# pcb-pick-plaz-feeder.net
KiCad netlist of a schematic drawn in EAGLE
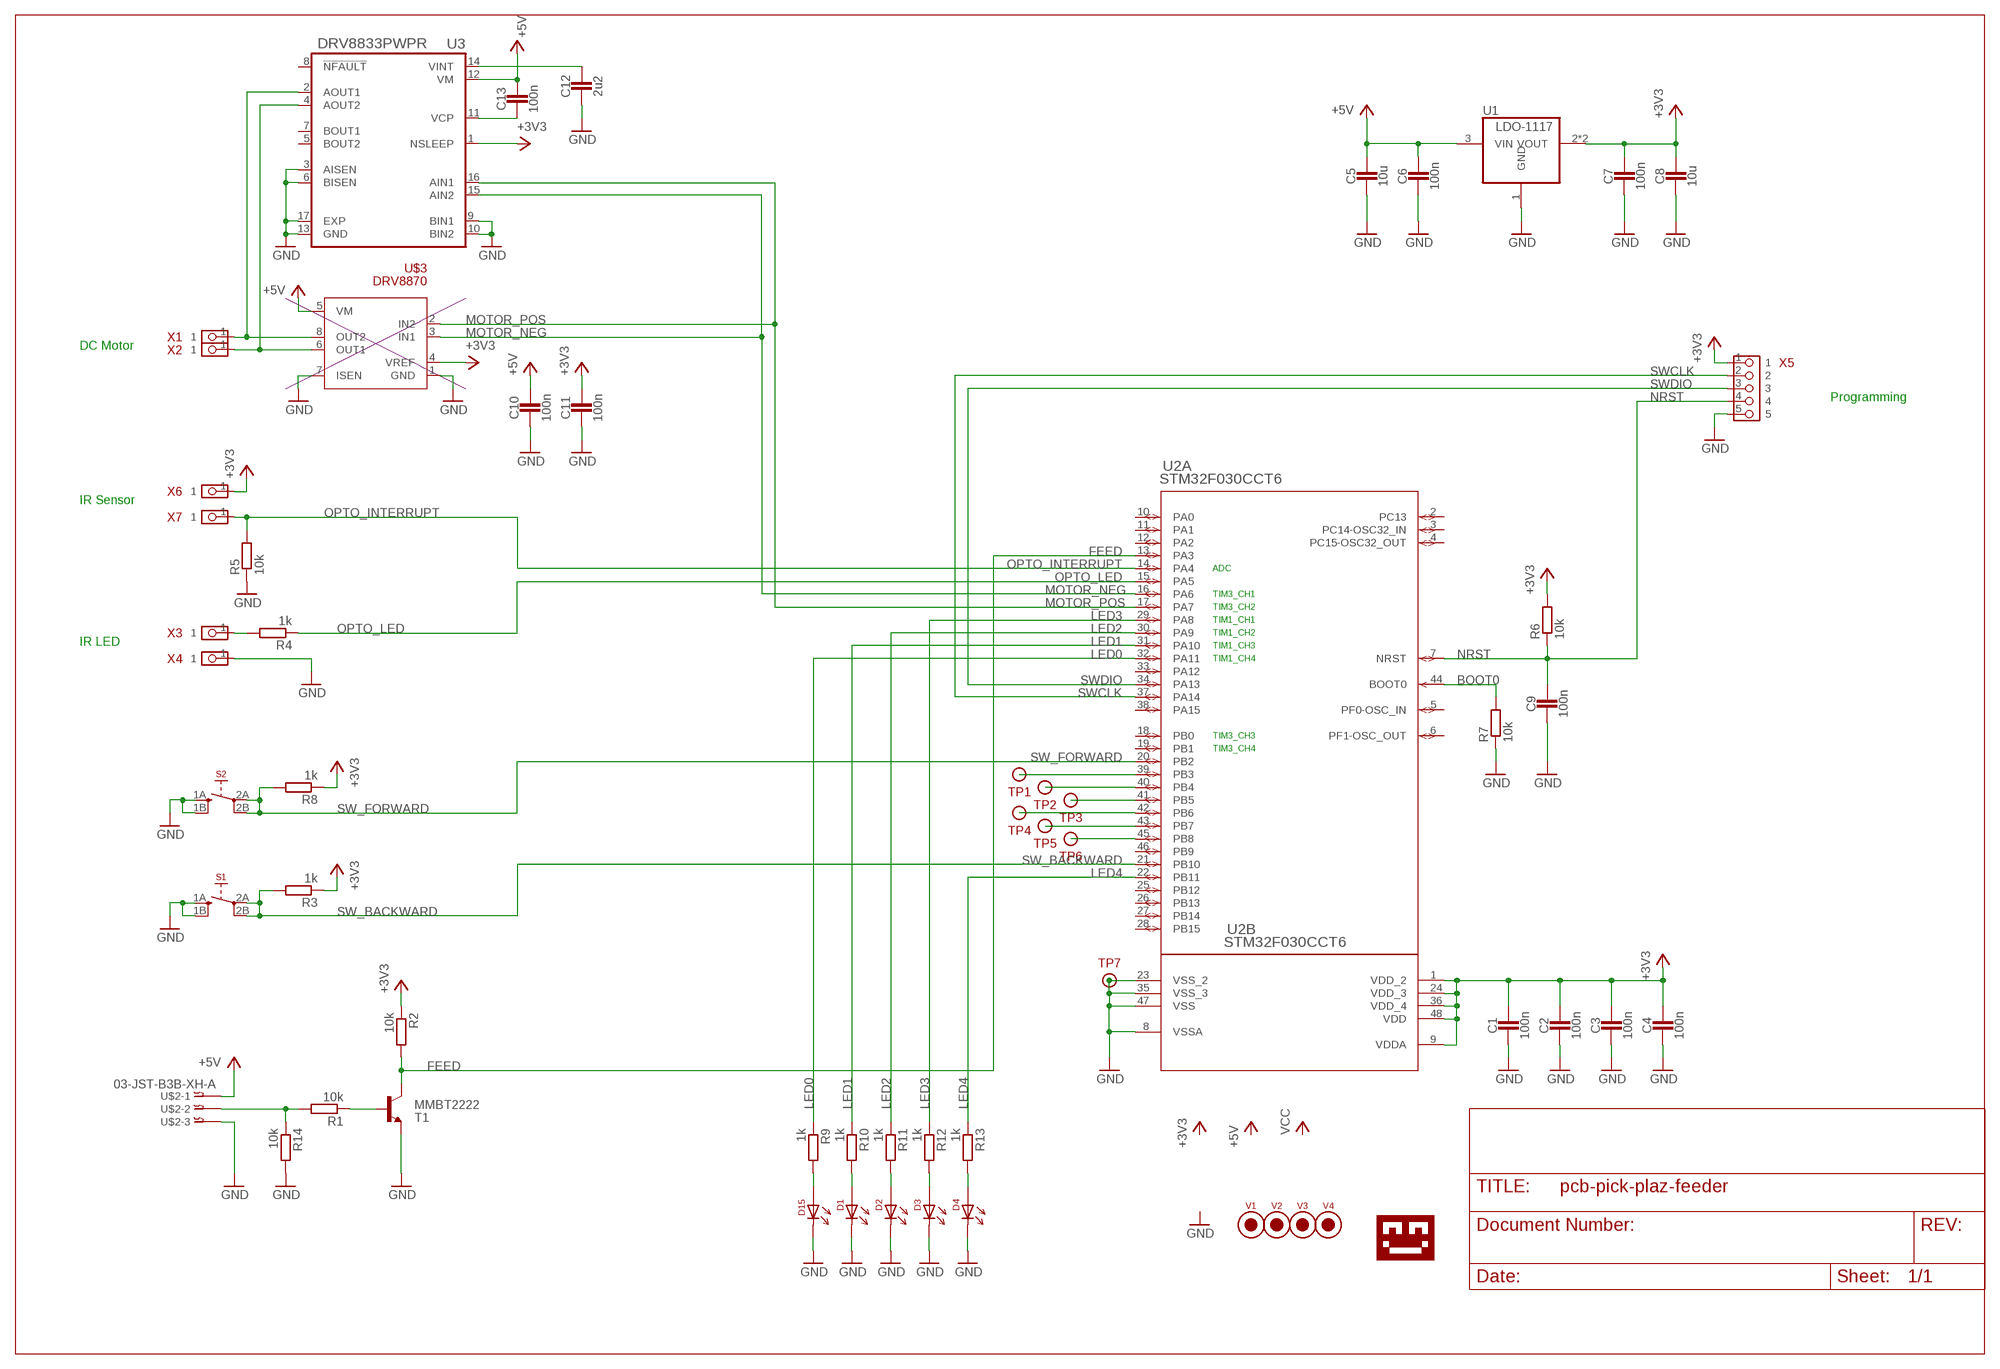
[diagram p0: schematic, sheet 1]

(export (version "E")
  (design (tool "Eeschema 10.0.6"))
  (components
    (comp (ref "C1")
      (value "100n")
      (footprint "eagle-import:0603_CAP")
      (libsource (lib "eagle-import") (part "CAPACITOR0603_CAP"))
    )
    (comp (ref "C2")
      (value "100n")
      (footprint "eagle-import:0603_CAP")
      (libsource (lib "eagle-import") (part "CAPACITOR0603_CAP"))
    )
    (comp (ref "C3")
      (value "100n")
      (footprint "eagle-import:0603_CAP")
      (libsource (lib "eagle-import") (part "CAPACITOR0603_CAP"))
    )
    (comp (ref "C4")
      (value "100n")
      (footprint "eagle-import:0603_CAP")
      (libsource (lib "eagle-import") (part "CAPACITOR0603_CAP"))
    )
    (comp (ref "C5")
      (value "10u")
      (footprint "eagle-import:0805_CAP")
      (libsource (lib "eagle-import") (part "CAPACITOR0805_CAP"))
    )
    (comp (ref "C6")
      (value "100n")
      (footprint "eagle-import:0603_CAP")
      (libsource (lib "eagle-import") (part "CAPACITOR0603_CAP"))
    )
    (comp (ref "C7")
      (value "100n")
      (footprint "eagle-import:0603_CAP")
      (libsource (lib "eagle-import") (part "CAPACITOR0603_CAP"))
    )
    (comp (ref "C8")
      (value "10u")
      (footprint "eagle-import:0805_CAP")
      (libsource (lib "eagle-import") (part "CAPACITOR0805_CAP"))
    )
    (comp (ref "C9")
      (value "100n")
      (footprint "eagle-import:0603_CAP")
      (libsource (lib "eagle-import") (part "CAPACITOR0603_CAP"))
    )
    (comp (ref "C10")
      (value "100n")
      (footprint "eagle-import:0603_CAP")
      (libsource (lib "eagle-import") (part "CAPACITOR0603_CAP"))
    )
    (comp (ref "C11")
      (value "100n")
      (footprint "eagle-import:0603_CAP")
      (libsource (lib "eagle-import") (part "CAPACITOR0603_CAP"))
    )
    (comp (ref "C12")
      (value "2u2")
      (footprint "eagle-import:0805_CAP")
      (libsource (lib "eagle-import") (part "CAPACITOR0805_CAP"))
    )
    (comp (ref "C13")
      (value "100n")
      (footprint "eagle-import:0603_CAP")
      (libsource (lib "eagle-import") (part "CAPACITOR0603_CAP"))
    )
    (comp (ref "D1")
      (value "LED-0805")
      (footprint "eagle-import:0805-DOT")
      (libsource (lib "eagle-import") (part "LED-0805"))
    )
    (comp (ref "D2")
      (value "LED-0805")
      (footprint "eagle-import:0805-DOT")
      (libsource (lib "eagle-import") (part "LED-0805"))
    )
    (comp (ref "D3")
      (value "LED-0805")
      (footprint "eagle-import:0805-DOT")
      (libsource (lib "eagle-import") (part "LED-0805"))
    )
    (comp (ref "D4")
      (value "LED-0805")
      (footprint "eagle-import:0805-DOT")
      (libsource (lib "eagle-import") (part "LED-0805"))
    )
    (comp (ref "D15")
      (value "LED-0805")
      (footprint "eagle-import:0805-DOT")
      (libsource (lib "eagle-import") (part "LED-0805"))
    )
    (comp (ref "R1")
      (value "10k")
      (footprint "eagle-import:0603-RES")
      (libsource (lib "eagle-import") (part "RESISTOR0603_RES"))
    )
    (comp (ref "R2")
      (value "10k")
      (footprint "eagle-import:0603-RES")
      (libsource (lib "eagle-import") (part "RESISTOR0603_RES"))
    )
    (comp (ref "R3")
      (value "1k")
      (footprint "eagle-import:0603-RES")
      (libsource (lib "eagle-import") (part "RESISTOR0603_RES"))
    )
    (comp (ref "R4")
      (value "1k")
      (footprint "eagle-import:0603-RES")
      (libsource (lib "eagle-import") (part "RESISTOR0603_RES"))
    )
    (comp (ref "R5")
      (value "10k")
      (footprint "eagle-import:0603-RES")
      (libsource (lib "eagle-import") (part "RESISTOR0603_RES"))
    )
    (comp (ref "R6")
      (value "10k")
      (footprint "eagle-import:0603-RES")
      (libsource (lib "eagle-import") (part "RESISTOR0603_RES"))
    )
    (comp (ref "R7")
      (value "10k")
      (footprint "eagle-import:0603-RES")
      (libsource (lib "eagle-import") (part "RESISTOR0603_RES"))
    )
    (comp (ref "R8")
      (value "1k")
      (footprint "eagle-import:0603-RES")
      (libsource (lib "eagle-import") (part "RESISTOR0603_RES"))
    )
    (comp (ref "R9")
      (value "1k")
      (footprint "eagle-import:0603-RES")
      (libsource (lib "eagle-import") (part "RESISTOR0603_RES"))
    )
    (comp (ref "R10")
      (value "1k")
      (footprint "eagle-import:0603-RES")
      (libsource (lib "eagle-import") (part "RESISTOR0603_RES"))
    )
    (comp (ref "R11")
      (value "1k")
      (footprint "eagle-import:0603-RES")
      (libsource (lib "eagle-import") (part "RESISTOR0603_RES"))
    )
    (comp (ref "R12")
      (value "1k")
      (footprint "eagle-import:0603-RES")
      (libsource (lib "eagle-import") (part "RESISTOR0603_RES"))
    )
    (comp (ref "R13")
      (value "1k")
      (footprint "eagle-import:0603-RES")
      (libsource (lib "eagle-import") (part "RESISTOR0603_RES"))
    )
    (comp (ref "R14")
      (value "10k")
      (footprint "eagle-import:0603-RES")
      (libsource (lib "eagle-import") (part "RESISTOR0603_RES"))
    )
    (comp (ref "S1")
      (value "SWITCH_2PD")
      (footprint "eagle-import:SWITCH_WH")
      (libsource (lib "eagle-import") (part "SWITCH_2PD"))
    )
    (comp (ref "S2")
      (value "SWITCH_2PD")
      (footprint "eagle-import:SWITCH_WH")
      (libsource (lib "eagle-import") (part "SWITCH_2PD"))
    )
    (comp (ref "T1")
      (value "MMBT2222")
      (footprint "eagle-import:SOT23-BEC")
      (libsource (lib "eagle-import") (part "-NPN-SOT23-BECMMBT2222ALT1"))
    )
    (comp (ref "TP1")
      (value "TESTPIN")
      (footprint "eagle-import:PIN-SMD-1X1-TEST_1M5")
      (libsource (lib "eagle-import") (part "TESTPIN"))
    )
    (comp (ref "TP2")
      (value "TESTPIN")
      (footprint "eagle-import:PIN-SMD-1X1-TEST_1M5")
      (libsource (lib "eagle-import") (part "TESTPIN"))
    )
    (comp (ref "TP3")
      (value "TESTPIN")
      (footprint "eagle-import:PIN-SMD-1X1-TEST_1M5")
      (libsource (lib "eagle-import") (part "TESTPIN"))
    )
    (comp (ref "TP4")
      (value "TESTPIN")
      (footprint "eagle-import:PIN-SMD-1X1-TEST_1M5")
      (libsource (lib "eagle-import") (part "TESTPIN"))
    )
    (comp (ref "TP5")
      (value "TESTPIN")
      (footprint "eagle-import:PIN-SMD-1X1-TEST_1M5")
      (libsource (lib "eagle-import") (part "TESTPIN"))
    )
    (comp (ref "TP6")
      (value "TESTPIN")
      (footprint "eagle-import:PIN-SMD-1X1-TEST_1M5")
      (libsource (lib "eagle-import") (part "TESTPIN"))
    )
    (comp (ref "TP7")
      (value "TESTPIN")
      (footprint "eagle-import:PIN-SMD-1X1-TEST_1M5")
      (libsource (lib "eagle-import") (part "TESTPIN"))
    )
    (comp (ref "U$1")
      (value "LOGO-TOBENG-1MM-FINISH")
      (footprint "eagle-import:TOBENG-1MM-FINISH")
      (libsource (lib "eagle-import") (part "LOGO-TOBENG-1MM-FINISH"))
    )
    (comp (ref "U$2")
      (value "03-JST-B3B-XH-A")
      (footprint "eagle-import:B3B-XH")
      (libsource (lib "eagle-import") (part "03-JST-B3B-XH-A"))
    )
    (comp (ref "U$3")
      (value "DRV8870")
      (footprint "eagle-import:SOIC-8")
      (libsource (lib "eagle-import") (part "DRV8870"))
    )
    (comp (ref "U1")
      (value "LDO-1117")
      (footprint "eagle-import:SOT-89")
      (libsource (lib "eagle-import") (part "LDO-1117"))
    )
    (comp (ref "U2")
      (value "STM32F030CCT6")
      (footprint "eagle-import:LQFP48-7X7MM")
      (fields (field (name "COPYRIGHT") "Copyright (C) 2018 Accelerated Designs. All rights reserved"))
      (libsource (lib "eagle-import") (part "STM32F030CCT6"))
    )
    (comp (ref "U3")
      (value "DRV8833PWPR")
      (footprint "eagle-import:IC_DRV8833PWPR")
      (fields (field (name "MF") "Texas Instruments"))
      (libsource (lib "eagle-import") (part "DRV8833PWPR"))
    )
    (comp (ref "V1")
      (value "FIDUCIAL2MM")
      (footprint "eagle-import:FIDUCIAL_2MM")
      (libsource (lib "eagle-import") (part "FIDUCIAL2MM"))
    )
    (comp (ref "V2")
      (value "FIDUCIAL2MM")
      (footprint "eagle-import:FIDUCIAL_2MM")
      (libsource (lib "eagle-import") (part "FIDUCIAL2MM"))
    )
    (comp (ref "V3")
      (value "FIDUCIAL2MM")
      (footprint "eagle-import:FIDUCIAL_2MM")
      (libsource (lib "eagle-import") (part "FIDUCIAL2MM"))
    )
    (comp (ref "V4")
      (value "FIDUCIAL2MM")
      (footprint "eagle-import:FIDUCIAL_2MM")
      (libsource (lib "eagle-import") (part "FIDUCIAL2MM"))
    )
    (comp (ref "X1")
      (value "PIN_1X1SMD_BIG_L")
      (footprint "eagle-import:PIN_1X1_SMD_BIG_L")
      (libsource (lib "eagle-import") (part "PIN_1X1SMD_BIG_L"))
    )
    (comp (ref "X2")
      (value "PIN_1X1SMD_BIG_L")
      (footprint "eagle-import:PIN_1X1_SMD_BIG_L")
      (libsource (lib "eagle-import") (part "PIN_1X1SMD_BIG_L"))
    )
    (comp (ref "X3")
      (value "PIN_1X1SMD_BIG_L")
      (footprint "eagle-import:PIN_1X1_SMD_BIG_L")
      (libsource (lib "eagle-import") (part "PIN_1X1SMD_BIG_L"))
    )
    (comp (ref "X4")
      (value "PIN_1X1SMD_BIG_L")
      (footprint "eagle-import:PIN_1X1_SMD_BIG_L")
      (libsource (lib "eagle-import") (part "PIN_1X1SMD_BIG_L"))
    )
    (comp (ref "X5")
      (value "PIN_5X1HD")
      (footprint "eagle-import:PIN_5X1_HD")
      (libsource (lib "eagle-import") (part "PIN_5X1HD"))
    )
    (comp (ref "X6")
      (value "PIN_1X1SMD_BIG_L")
      (footprint "eagle-import:PIN_1X1_SMD_BIG_L")
      (libsource (lib "eagle-import") (part "PIN_1X1SMD_BIG_L"))
    )
    (comp (ref "X7")
      (value "PIN_1X1SMD_BIG_L")
      (footprint "eagle-import:PIN_1X1_SMD_BIG_L")
      (libsource (lib "eagle-import") (part "PIN_1X1SMD_BIG_L"))
    )
  )
  (nets
    (net (code "1") (name "+3V3") (class "Default")
      (node (ref "C1") (pin "1") (pinfunction "1_1") (pintype "bidirectional"))
      (node (ref "C11") (pin "1") (pinfunction "1_1") (pintype "bidirectional"))
      (node (ref "C2") (pin "1") (pinfunction "1_1") (pintype "bidirectional"))
      (node (ref "C3") (pin "1") (pinfunction "1_1") (pintype "bidirectional"))
      (node (ref "C4") (pin "1") (pinfunction "1_1") (pintype "bidirectional"))
      (node (ref "C7") (pin "1") (pinfunction "1_1") (pintype "bidirectional"))
      (node (ref "C8") (pin "P$1") (pinfunction "1_P$1") (pintype "bidirectional"))
      (node (ref "R2") (pin "1") (pinfunction "1_1") (pintype "passive"))
      (node (ref "R3") (pin "1") (pinfunction "1_1") (pintype "passive"))
      (node (ref "R6") (pin "2") (pinfunction "2_2") (pintype "passive"))
      (node (ref "R8") (pin "1") (pinfunction "1_1") (pintype "passive"))
      (node (ref "U$3") (pin "4") (pinfunction "VREF_4") (pintype "bidirectional"))
      (node (ref "U1") (pin "2") (pinfunction "VOUT_2") (pintype "output"))
      (node (ref "U1") (pin "2@1") (pinfunction "VOUT_2@1") (pintype "output"))
      (node (ref "U2") (pin "1") (pinfunction "VDD_2_1") (pintype "power_in"))
      (node (ref "U2") (pin "24") (pinfunction "VDD_3_24") (pintype "power_in"))
      (node (ref "U2") (pin "36") (pinfunction "VDD_4_36") (pintype "power_in"))
      (node (ref "U2") (pin "48") (pinfunction "VDD_48") (pintype "power_in"))
      (node (ref "U2") (pin "9") (pinfunction "VDDA_9") (pintype "power_in"))
      (node (ref "U3") (pin "1") (pinfunction "NSLEEP_1") (pintype "input"))
      (node (ref "X5") (pin "1") (pinfunction "1_1") (pintype "bidirectional"))
      (node (ref "X6") (pin "1") (pinfunction "1_1") (pintype "bidirectional"))
    )
    (net (code "2") (name "+5V") (class "Default")
      (node (ref "C10") (pin "1") (pinfunction "1_1") (pintype "bidirectional"))
      (node (ref "C13") (pin "1") (pinfunction "1_1") (pintype "bidirectional"))
      (node (ref "C5") (pin "P$1") (pinfunction "1_P$1") (pintype "bidirectional"))
      (node (ref "C6") (pin "1") (pinfunction "1_1") (pintype "bidirectional"))
      (node (ref "U$2") (pin "P$1") (pinfunction "1_P$1") (pintype "passive"))
      (node (ref "U$3") (pin "5") (pinfunction "VM_5") (pintype "bidirectional"))
      (node (ref "U1") (pin "3") (pinfunction "VIN_3") (pintype "input"))
      (node (ref "U3") (pin "12") (pinfunction "VM_12") (pintype "power_in"))
    )
    (net (code "3") (name "/BOOT0") (class "Default")
      (node (ref "R7") (pin "2") (pinfunction "2_2") (pintype "passive"))
      (node (ref "U2") (pin "44") (pinfunction "BOOT0_44") (pintype "input"))
    )
    (net (code "4") (name "/FEED") (class "Default")
      (node (ref "R2") (pin "2") (pinfunction "2_2") (pintype "passive"))
      (node (ref "T1") (pin "C") (pinfunction "C_C") (pintype "passive"))
      (node (ref "U2") (pin "13") (pinfunction "PA3_13") (pintype "bidirectional"))
    )
    (net (code "5") (name "/LED0") (class "Default")
      (node (ref "R9") (pin "1") (pinfunction "1_1") (pintype "passive"))
      (node (ref "U2") (pin "32") (pinfunction "PA11_32") (pintype "bidirectional"))
    )
    (net (code "6") (name "/LED1") (class "Default")
      (node (ref "R10") (pin "1") (pinfunction "1_1") (pintype "passive"))
      (node (ref "U2") (pin "31") (pinfunction "PA10_31") (pintype "bidirectional"))
    )
    (net (code "7") (name "/LED2") (class "Default")
      (node (ref "R11") (pin "1") (pinfunction "1_1") (pintype "passive"))
      (node (ref "U2") (pin "30") (pinfunction "PA9_30") (pintype "bidirectional"))
    )
    (net (code "8") (name "/LED3") (class "Default")
      (node (ref "R12") (pin "1") (pinfunction "1_1") (pintype "passive"))
      (node (ref "U2") (pin "29") (pinfunction "PA8_29") (pintype "bidirectional"))
    )
    (net (code "9") (name "/LED4") (class "Default")
      (node (ref "R13") (pin "1") (pinfunction "1_1") (pintype "passive"))
      (node (ref "U2") (pin "22") (pinfunction "PB11_22") (pintype "bidirectional"))
    )
    (net (code "10") (name "/MOTOR_NEG") (class "Default")
      (node (ref "U$3") (pin "3") (pinfunction "IN1_3") (pintype "bidirectional"))
      (node (ref "U2") (pin "16") (pinfunction "PA6_16") (pintype "bidirectional"))
      (node (ref "U3") (pin "15") (pinfunction "AIN2_15") (pintype "input"))
    )
    (net (code "11") (name "/MOTOR_POS") (class "Default")
      (node (ref "U$3") (pin "2") (pinfunction "IN2_2") (pintype "bidirectional"))
      (node (ref "U2") (pin "17") (pinfunction "PA7_17") (pintype "bidirectional"))
      (node (ref "U3") (pin "16") (pinfunction "AIN1_16") (pintype "input"))
    )
    (net (code "12") (name "/NRST") (class "Default")
      (node (ref "C9") (pin "1") (pinfunction "1_1") (pintype "bidirectional"))
      (node (ref "R6") (pin "1") (pinfunction "1_1") (pintype "passive"))
      (node (ref "U2") (pin "7") (pinfunction "NRST_7") (pintype "bidirectional"))
      (node (ref "X5") (pin "4") (pinfunction "4_4") (pintype "bidirectional"))
    )
    (net (code "13") (name "/OPTO_INTERRUPT") (class "Default")
      (node (ref "R5") (pin "2") (pinfunction "2_2") (pintype "passive"))
      (node (ref "U2") (pin "14") (pinfunction "PA4_14") (pintype "bidirectional"))
      (node (ref "X7") (pin "1") (pinfunction "1_1") (pintype "bidirectional"))
    )
    (net (code "14") (name "/OPTO_LED") (class "Default")
      (node (ref "R4") (pin "1") (pinfunction "1_1") (pintype "passive"))
      (node (ref "U2") (pin "15") (pinfunction "PA5_15") (pintype "bidirectional"))
    )
    (net (code "15") (name "/SWCLK") (class "Default")
      (node (ref "U2") (pin "37") (pinfunction "PA14_37") (pintype "bidirectional"))
      (node (ref "X5") (pin "2") (pinfunction "2_2") (pintype "bidirectional"))
    )
    (net (code "16") (name "/SWDIO") (class "Default")
      (node (ref "U2") (pin "34") (pinfunction "PA13_34") (pintype "bidirectional"))
      (node (ref "X5") (pin "3") (pinfunction "3_3") (pintype "bidirectional"))
    )
    (net (code "17") (name "/SW_BACKWARD") (class "Default")
      (node (ref "R3") (pin "2") (pinfunction "2_2") (pintype "passive"))
      (node (ref "S1") (pin "2A") (pinfunction "3_2A") (pintype "bidirectional"))
      (node (ref "S1") (pin "2B") (pinfunction "4_2B") (pintype "bidirectional"))
      (node (ref "U2") (pin "21") (pinfunction "PB10_21") (pintype "bidirectional"))
    )
    (net (code "18") (name "/SW_FORWARD") (class "Default")
      (node (ref "R8") (pin "2") (pinfunction "2_2") (pintype "passive"))
      (node (ref "S2") (pin "2A") (pinfunction "3_2A") (pintype "bidirectional"))
      (node (ref "S2") (pin "2B") (pinfunction "4_2B") (pintype "bidirectional"))
      (node (ref "U2") (pin "20") (pinfunction "PB2_20") (pintype "bidirectional"))
    )
    (net (code "19") (name "GND") (class "Default")
      (node (ref "C1") (pin "2") (pinfunction "2_2") (pintype "bidirectional"))
      (node (ref "C10") (pin "2") (pinfunction "2_2") (pintype "bidirectional"))
      (node (ref "C11") (pin "2") (pinfunction "2_2") (pintype "bidirectional"))
      (node (ref "C12") (pin "P$2") (pinfunction "2_P$2") (pintype "bidirectional"))
      (node (ref "C2") (pin "2") (pinfunction "2_2") (pintype "bidirectional"))
      (node (ref "C3") (pin "2") (pinfunction "2_2") (pintype "bidirectional"))
      (node (ref "C4") (pin "2") (pinfunction "2_2") (pintype "bidirectional"))
      (node (ref "C5") (pin "P$2") (pinfunction "2_P$2") (pintype "bidirectional"))
      (node (ref "C6") (pin "2") (pinfunction "2_2") (pintype "bidirectional"))
      (node (ref "C7") (pin "2") (pinfunction "2_2") (pintype "bidirectional"))
      (node (ref "C8") (pin "P$2") (pinfunction "2_P$2") (pintype "bidirectional"))
      (node (ref "C9") (pin "2") (pinfunction "2_2") (pintype "bidirectional"))
      (node (ref "D1") (pin "2") (pinfunction "2_2") (pintype "bidirectional"))
      (node (ref "D15") (pin "2") (pinfunction "2_2") (pintype "bidirectional"))
      (node (ref "D2") (pin "2") (pinfunction "2_2") (pintype "bidirectional"))
      (node (ref "D3") (pin "2") (pinfunction "2_2") (pintype "bidirectional"))
      (node (ref "D4") (pin "2") (pinfunction "2_2") (pintype "bidirectional"))
      (node (ref "R14") (pin "2") (pinfunction "2_2") (pintype "passive"))
      (node (ref "R5") (pin "1") (pinfunction "1_1") (pintype "passive"))
      (node (ref "R7") (pin "1") (pinfunction "1_1") (pintype "passive"))
      (node (ref "S1") (pin "1A") (pinfunction "1_1A") (pintype "bidirectional"))
      (node (ref "S1") (pin "1B") (pinfunction "2_1B") (pintype "bidirectional"))
      (node (ref "S2") (pin "1A") (pinfunction "1_1A") (pintype "bidirectional"))
      (node (ref "S2") (pin "1B") (pinfunction "2_1B") (pintype "bidirectional"))
      (node (ref "T1") (pin "E") (pinfunction "E_E") (pintype "passive"))
      (node (ref "TP7") (pin "1") (pinfunction "1_1") (pintype "bidirectional"))
      (node (ref "U$2") (pin "P$3") (pinfunction "1_P$3") (pintype "passive"))
      (node (ref "U$3") (pin "1") (pinfunction "GND_1") (pintype "bidirectional"))
      (node (ref "U$3") (pin "7") (pinfunction "ISEN_7") (pintype "bidirectional"))
      (node (ref "U1") (pin "1") (pinfunction "GND_1") (pintype "power_in"))
      (node (ref "U2") (pin "23") (pinfunction "VSS_2_23") (pintype "power_in"))
      (node (ref "U2") (pin "35") (pinfunction "VSS_3_35") (pintype "power_in"))
      (node (ref "U2") (pin "47") (pinfunction "VSS_47") (pintype "power_in"))
      (node (ref "U2") (pin "8") (pinfunction "VSSA_8") (pintype "power_in"))
      (node (ref "U3") (pin "10") (pinfunction "BIN2_10") (pintype "input"))
      (node (ref "U3") (pin "13") (pinfunction "GND_13") (pintype "power_in"))
      (node (ref "U3") (pin "17") (pinfunction "EXP_17") (pintype "passive"))
      (node (ref "U3") (pin "3") (pinfunction "AISEN_3") (pintype "bidirectional"))
      (node (ref "U3") (pin "6") (pinfunction "BISEN_6") (pintype "bidirectional"))
      (node (ref "U3") (pin "9") (pinfunction "BIN1_9") (pintype "input"))
      (node (ref "X4") (pin "1") (pinfunction "1_1") (pintype "bidirectional"))
      (node (ref "X5") (pin "5") (pinfunction "5_5") (pintype "bidirectional"))
    )
    (net (code "20") (name "Net-(C12-1)") (class "Default")
      (node (ref "C12") (pin "P$1") (pinfunction "1_P$1") (pintype "bidirectional"))
      (node (ref "U3") (pin "14") (pinfunction "VINT_14") (pintype "power_in"))
    )
    (net (code "21") (name "Net-(D1-Pad1)") (class "Default")
      (node (ref "D1") (pin "1") (pinfunction "1_1") (pintype "bidirectional"))
      (node (ref "R10") (pin "2") (pinfunction "2_2") (pintype "passive"))
    )
    (net (code "22") (name "Net-(D2-Pad1)") (class "Default")
      (node (ref "D2") (pin "1") (pinfunction "1_1") (pintype "bidirectional"))
      (node (ref "R11") (pin "2") (pinfunction "2_2") (pintype "passive"))
    )
    (net (code "23") (name "Net-(D3-Pad1)") (class "Default")
      (node (ref "D3") (pin "1") (pinfunction "1_1") (pintype "bidirectional"))
      (node (ref "R12") (pin "2") (pinfunction "2_2") (pintype "passive"))
    )
    (net (code "24") (name "Net-(D4-Pad1)") (class "Default")
      (node (ref "D4") (pin "1") (pinfunction "1_1") (pintype "bidirectional"))
      (node (ref "R13") (pin "2") (pinfunction "2_2") (pintype "passive"))
    )
    (net (code "25") (name "Net-(D15-Pad1)") (class "Default")
      (node (ref "D15") (pin "1") (pinfunction "1_1") (pintype "bidirectional"))
      (node (ref "R9") (pin "2") (pinfunction "2_2") (pintype "passive"))
    )
    (net (code "26") (name "Net-(R1-Pad1)") (class "Default")
      (node (ref "R1") (pin "1") (pinfunction "1_1") (pintype "passive"))
      (node (ref "T1") (pin "B") (pinfunction "B_B") (pintype "passive"))
    )
    (net (code "27") (name "Net-(R4-Pad2)") (class "Default")
      (node (ref "R4") (pin "2") (pinfunction "2_2") (pintype "passive"))
      (node (ref "X3") (pin "1") (pinfunction "1_1") (pintype "bidirectional"))
    )
    (net (code "28") (name "Net-(U$2B-1)") (class "Default")
      (node (ref "R1") (pin "2") (pinfunction "2_2") (pintype "passive"))
      (node (ref "R14") (pin "1") (pinfunction "1_1") (pintype "passive"))
      (node (ref "U$2") (pin "P$2") (pinfunction "1_P$2") (pintype "passive"))
    )
    (net (code "29") (name "Net-(U$3-OUT1)") (class "Default")
      (node (ref "U$3") (pin "6") (pinfunction "OUT1_6") (pintype "bidirectional"))
      (node (ref "U3") (pin "4") (pinfunction "AOUT2_4") (pintype "output"))
      (node (ref "X2") (pin "1") (pinfunction "1_1") (pintype "bidirectional"))
    )
    (net (code "30") (name "Net-(U$3-OUT2)") (class "Default")
      (node (ref "U$3") (pin "8") (pinfunction "OUT2_8") (pintype "bidirectional"))
      (node (ref "U3") (pin "2") (pinfunction "AOUT1_2") (pintype "output"))
      (node (ref "X1") (pin "1") (pinfunction "1_1") (pintype "bidirectional"))
    )
    (net (code "31") (name "Net-(U2A-PB3)") (class "Default")
      (node (ref "TP1") (pin "1") (pinfunction "1_1") (pintype "bidirectional"))
      (node (ref "U2") (pin "39") (pinfunction "PB3_39") (pintype "bidirectional"))
    )
    (net (code "32") (name "Net-(U2A-PB4)") (class "Default")
      (node (ref "TP2") (pin "1") (pinfunction "1_1") (pintype "bidirectional"))
      (node (ref "U2") (pin "40") (pinfunction "PB4_40") (pintype "bidirectional"))
    )
    (net (code "33") (name "Net-(U2A-PB5)") (class "Default")
      (node (ref "TP3") (pin "1") (pinfunction "1_1") (pintype "bidirectional"))
      (node (ref "U2") (pin "41") (pinfunction "PB5_41") (pintype "bidirectional"))
    )
    (net (code "34") (name "Net-(U2A-PB6)") (class "Default")
      (node (ref "TP4") (pin "1") (pinfunction "1_1") (pintype "bidirectional"))
      (node (ref "U2") (pin "42") (pinfunction "PB6_42") (pintype "bidirectional"))
    )
    (net (code "35") (name "Net-(U2A-PB7)") (class "Default")
      (node (ref "TP5") (pin "1") (pinfunction "1_1") (pintype "bidirectional"))
      (node (ref "U2") (pin "43") (pinfunction "PB7_43") (pintype "bidirectional"))
    )
    (net (code "36") (name "Net-(U2A-PB8)") (class "Default")
      (node (ref "TP6") (pin "1") (pinfunction "1_1") (pintype "bidirectional"))
      (node (ref "U2") (pin "45") (pinfunction "PB8_45") (pintype "bidirectional"))
    )
    (net (code "37") (name "Net-(U3-VCP)") (class "Default")
      (node (ref "C13") (pin "2") (pinfunction "2_2") (pintype "bidirectional"))
      (node (ref "U3") (pin "11") (pinfunction "VCP_11") (pintype "bidirectional"))
    )
    (net (code "39") (name "unconnected-(U2A-PA0-Pad10)") (class "Default")
      (node (ref "U2") (pin "10") (pinfunction "PA0_10") (pintype "bidirectional"))
    )
    (net (code "40") (name "unconnected-(U2A-PA1-Pad11)") (class "Default")
      (node (ref "U2") (pin "11") (pinfunction "PA1_11") (pintype "bidirectional"))
    )
    (net (code "41") (name "unconnected-(U2A-PA2-Pad12)") (class "Default")
      (node (ref "U2") (pin "12") (pinfunction "PA2_12") (pintype "bidirectional"))
    )
    (net (code "42") (name "unconnected-(U2A-PA12-Pad33)") (class "Default")
      (node (ref "U2") (pin "33") (pinfunction "PA12_33") (pintype "bidirectional"))
    )
    (net (code "43") (name "unconnected-(U2A-PA15-Pad38)") (class "Default")
      (node (ref "U2") (pin "38") (pinfunction "PA15_38") (pintype "bidirectional"))
    )
    (net (code "44") (name "unconnected-(U2A-PB0-Pad18)") (class "Default")
      (node (ref "U2") (pin "18") (pinfunction "PB0_18") (pintype "bidirectional"))
    )
    (net (code "45") (name "unconnected-(U2A-PB1-Pad19)") (class "Default")
      (node (ref "U2") (pin "19") (pinfunction "PB1_19") (pintype "bidirectional"))
    )
    (net (code "46") (name "unconnected-(U2A-PB9-Pad46)") (class "Default")
      (node (ref "U2") (pin "46") (pinfunction "PB9_46") (pintype "bidirectional"))
    )
    (net (code "47") (name "unconnected-(U2A-PB12-Pad25)") (class "Default")
      (node (ref "U2") (pin "25") (pinfunction "PB12_25") (pintype "bidirectional"))
    )
    (net (code "48") (name "unconnected-(U2A-PB13-Pad26)") (class "Default")
      (node (ref "U2") (pin "26") (pinfunction "PB13_26") (pintype "bidirectional"))
    )
    (net (code "49") (name "unconnected-(U2A-PB14-Pad27)") (class "Default")
      (node (ref "U2") (pin "27") (pinfunction "PB14_27") (pintype "bidirectional"))
    )
    (net (code "50") (name "unconnected-(U2A-PB15-Pad28)") (class "Default")
      (node (ref "U2") (pin "28") (pinfunction "PB15_28") (pintype "bidirectional"))
    )
    (net (code "51") (name "unconnected-(U2A-PC13-Pad2)") (class "Default")
      (node (ref "U2") (pin "2") (pinfunction "PC13_2") (pintype "bidirectional"))
    )
    (net (code "52") (name "unconnected-(U2A-PC14-OSC32_IN-Pad3)") (class "Default")
      (node (ref "U2") (pin "3") (pinfunction "PC14-OSC32_IN_3") (pintype "bidirectional"))
    )
    (net (code "53") (name "unconnected-(U2A-PC15-OSC32_OUT-Pad4)") (class "Default")
      (node (ref "U2") (pin "4") (pinfunction "PC15-OSC32_OUT_4") (pintype "bidirectional"))
    )
    (net (code "54") (name "unconnected-(U2A-PF0-OSC_IN-Pad5)") (class "Default")
      (node (ref "U2") (pin "5") (pinfunction "PF0-OSC_IN_5") (pintype "bidirectional"))
    )
    (net (code "55") (name "unconnected-(U2A-PF1-OSC_OUT-Pad6)") (class "Default")
      (node (ref "U2") (pin "6") (pinfunction "PF1-OSC_OUT_6") (pintype "bidirectional"))
    )
    (net (code "56") (name "unconnected-(U3-BOUT1-Pad7)") (class "Default")
      (node (ref "U3") (pin "7") (pinfunction "BOUT1_7") (pintype "output"))
    )
    (net (code "57") (name "unconnected-(U3-BOUT2-Pad5)") (class "Default")
      (node (ref "U3") (pin "5") (pinfunction "BOUT2_5") (pintype "output"))
    )
    (net (code "58") (name "unconnected-(U3-~{NFAULT}-Pad8)") (class "Default")
      (node (ref "U3") (pin "8") (pinfunction "~{NFAULT}_8") (pintype "output"))
    )
  )
)
